# Sparkfun_Qwiic_Shield_for_ESP32.net
KiCad netlist of a schematic drawn in EAGLE
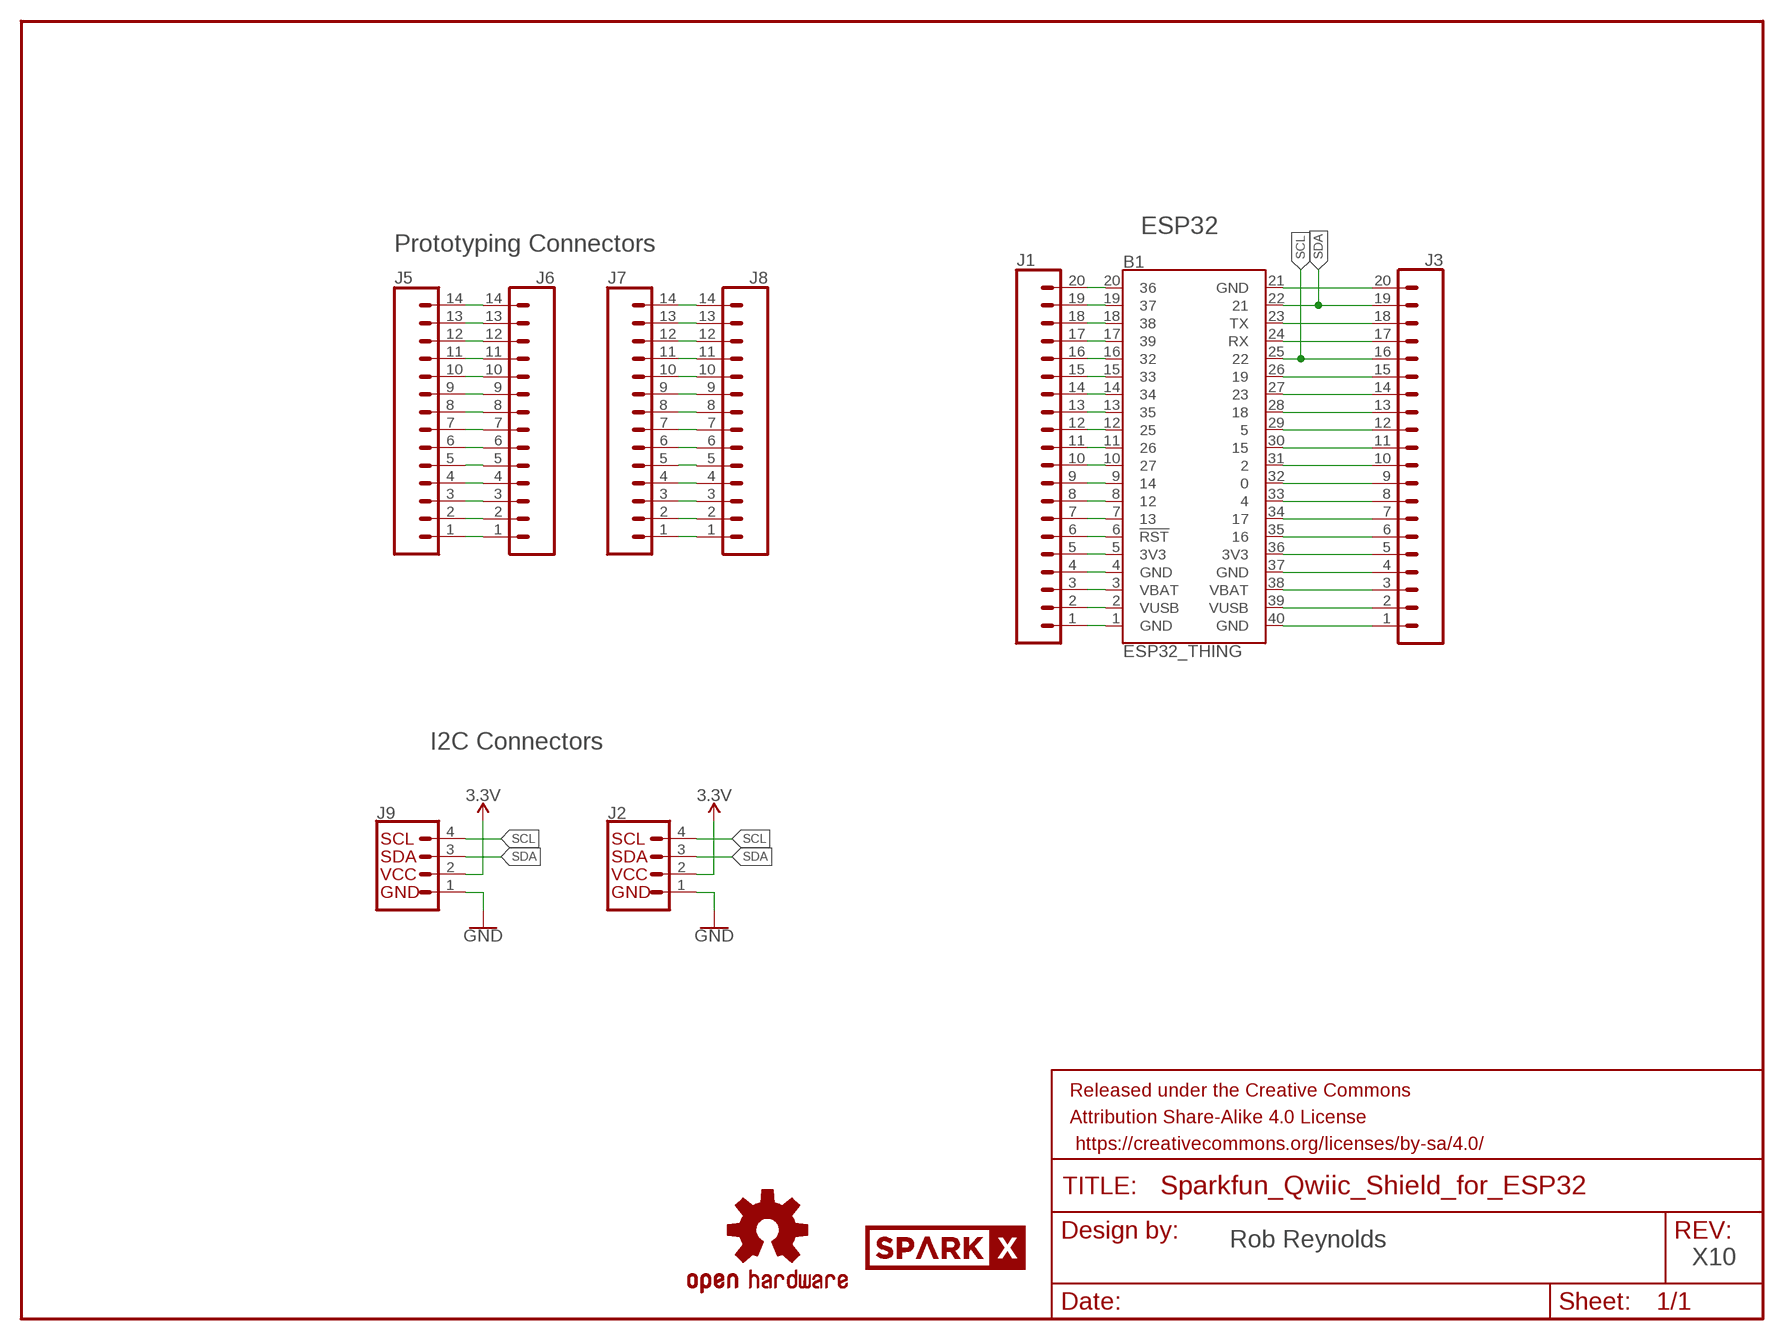
[diagram p0: schematic, sheet 1]

(export (version "E")
  (design (tool "Eeschema 10.0.6"))
  (components
    (comp (ref "B1")
      (value "ESP32_THING")
      (footprint "eagle-import:ESP32_THING")
      (libsource (lib "eagle-import") (part "ESP32_THING"))
    )
    (comp (ref "FRAME1")
      (value "FRAME-LETTERNO_PACKAGE")
      (footprint "eagle-import:DUMMY")
      (fields (field (name "DESIGNER") "Nobody"))
      (libsource (lib "eagle-import") (part "FRAME-LETTERNO_PACKAGE"))
    )
    (comp (ref "J1")
      (value "CONN_20NOSILK")
      (footprint "eagle-import:1X20_NOSILK")
      (libsource (lib "eagle-import") (part "CONN_20NOSILK"))
    )
    (comp (ref "J2")
      (value "I2C_STANDARDJS-1MM")
      (footprint "eagle-import:1X04_1MM_RA")
      (libsource (lib "eagle-import") (part "I2C_STANDARDJS-1MM"))
    )
    (comp (ref "J3")
      (value "CONN_20NOSILK")
      (footprint "eagle-import:1X20_NOSILK")
      (libsource (lib "eagle-import") (part "CONN_20NOSILK"))
    )
    (comp (ref "J5")
      (value "CONN_14NO_SILK")
      (footprint "eagle-import:1X14_NO_SILK")
      (libsource (lib "eagle-import") (part "CONN_14NO_SILK"))
    )
    (comp (ref "J6")
      (value "CONN_14NO_SILK")
      (footprint "eagle-import:1X14_NO_SILK")
      (libsource (lib "eagle-import") (part "CONN_14NO_SILK"))
    )
    (comp (ref "J7")
      (value "CONN_14NO_SILK")
      (footprint "eagle-import:1X14_NO_SILK")
      (libsource (lib "eagle-import") (part "CONN_14NO_SILK"))
    )
    (comp (ref "J8")
      (value "CONN_14NO_SILK")
      (footprint "eagle-import:1X14_NO_SILK")
      (libsource (lib "eagle-import") (part "CONN_14NO_SILK"))
    )
    (comp (ref "J9")
      (value "I2C_STANDARDJS-1MM")
      (footprint "eagle-import:1X04_1MM_RA")
      (libsource (lib "eagle-import") (part "I2C_STANDARDJS-1MM"))
    )
    (comp (ref "LOGO1")
      (value "OSHW-LOGOMINI")
      (footprint "eagle-import:OSHW-LOGO-MINI")
      (libsource (lib "eagle-import") (part "OSHW-LOGOMINI"))
    )
    (comp (ref "U$1")
      (value "SPARKX-LOGO3")
      (footprint "eagle-import:SPARKX-SMALL")
      (libsource (lib "eagle-import") (part "SPARKX-LOGO3"))
    )
  )
  (nets
    (net (code "1") (name "/VBAT") (class "Default")
      (node (ref "B1") (pin "3") (pinfunction "VBAT_3") (pintype "bidirectional"))
      (node (ref "B1") (pin "38") (pinfunction "VBAT_38") (pintype "bidirectional"))
      (node (ref "J1") (pin "3") (pinfunction "3_3") (pintype "passive"))
      (node (ref "J3") (pin "3") (pinfunction "3_3") (pintype "passive"))
    )
    (net (code "2") (name "/VUSB") (class "Default")
      (node (ref "B1") (pin "2") (pinfunction "VUSB_2") (pintype "bidirectional"))
      (node (ref "B1") (pin "39") (pinfunction "VUSB_39") (pintype "bidirectional"))
      (node (ref "J1") (pin "2") (pinfunction "2_2") (pintype "passive"))
      (node (ref "J3") (pin "2") (pinfunction "2_2") (pintype "passive"))
    )
    (net (code "3") (name "3.3V") (class "Default")
      (node (ref "B1") (pin "36") (pinfunction "3V3_36") (pintype "bidirectional"))
      (node (ref "B1") (pin "5") (pinfunction "3V3_5") (pintype "bidirectional"))
      (node (ref "J1") (pin "5") (pinfunction "5_5") (pintype "passive"))
      (node (ref "J2") (pin "2") (pinfunction "VCC_2") (pintype "power_in"))
      (node (ref "J3") (pin "5") (pinfunction "5_5") (pintype "passive"))
      (node (ref "J9") (pin "2") (pinfunction "VCC_2") (pintype "power_in"))
    )
    (net (code "4") (name "GND") (class "Default")
      (node (ref "B1") (pin "1") (pinfunction "GND_1") (pintype "bidirectional"))
      (node (ref "B1") (pin "21") (pinfunction "GND_21") (pintype "bidirectional"))
      (node (ref "B1") (pin "37") (pinfunction "GND_37") (pintype "bidirectional"))
      (node (ref "B1") (pin "4") (pinfunction "GND_4") (pintype "bidirectional"))
      (node (ref "B1") (pin "40") (pinfunction "GND_40") (pintype "bidirectional"))
      (node (ref "J1") (pin "1") (pinfunction "1_1") (pintype "passive"))
      (node (ref "J1") (pin "4") (pinfunction "4_4") (pintype "passive"))
      (node (ref "J2") (pin "1") (pinfunction "GND_1") (pintype "power_in"))
      (node (ref "J3") (pin "1") (pinfunction "1_1") (pintype "passive"))
      (node (ref "J3") (pin "20") (pinfunction "20_20") (pintype "passive"))
      (node (ref "J3") (pin "4") (pinfunction "4_4") (pintype "passive"))
      (node (ref "J9") (pin "1") (pinfunction "GND_1") (pintype "power_in"))
    )
    (net (code "5") (name "Net-(B1-0)") (class "Default")
      (node (ref "B1") (pin "32") (pinfunction "0_32") (pintype "bidirectional"))
      (node (ref "J3") (pin "9") (pinfunction "9_9") (pintype "passive"))
    )
    (net (code "6") (name "Net-(B1-2)") (class "Default")
      (node (ref "B1") (pin "31") (pinfunction "2_31") (pintype "bidirectional"))
      (node (ref "J3") (pin "10") (pinfunction "10_10") (pintype "passive"))
    )
    (net (code "7") (name "Net-(B1-4)") (class "Default")
      (node (ref "B1") (pin "33") (pinfunction "4_33") (pintype "bidirectional"))
      (node (ref "J3") (pin "8") (pinfunction "8_8") (pintype "passive"))
    )
    (net (code "8") (name "Net-(B1-5)") (class "Default")
      (node (ref "B1") (pin "29") (pinfunction "5_29") (pintype "bidirectional"))
      (node (ref "J3") (pin "12") (pinfunction "12_12") (pintype "passive"))
    )
    (net (code "9") (name "Net-(B1-12)") (class "Default")
      (node (ref "B1") (pin "8") (pinfunction "12_8") (pintype "bidirectional"))
      (node (ref "J1") (pin "8") (pinfunction "8_8") (pintype "passive"))
    )
    (net (code "10") (name "Net-(B1-13)") (class "Default")
      (node (ref "B1") (pin "7") (pinfunction "13_7") (pintype "bidirectional"))
      (node (ref "J1") (pin "7") (pinfunction "7_7") (pintype "passive"))
    )
    (net (code "11") (name "Net-(B1-14)") (class "Default")
      (node (ref "B1") (pin "9") (pinfunction "14_9") (pintype "bidirectional"))
      (node (ref "J1") (pin "9") (pinfunction "9_9") (pintype "passive"))
    )
    (net (code "12") (name "Net-(B1-15)") (class "Default")
      (node (ref "B1") (pin "30") (pinfunction "15_30") (pintype "bidirectional"))
      (node (ref "J3") (pin "11") (pinfunction "11_11") (pintype "passive"))
    )
    (net (code "13") (name "Net-(B1-16)") (class "Default")
      (node (ref "B1") (pin "35") (pinfunction "16_35") (pintype "bidirectional"))
      (node (ref "J3") (pin "6") (pinfunction "6_6") (pintype "passive"))
    )
    (net (code "14") (name "Net-(B1-17)") (class "Default")
      (node (ref "B1") (pin "34") (pinfunction "17_34") (pintype "bidirectional"))
      (node (ref "J3") (pin "7") (pinfunction "7_7") (pintype "passive"))
    )
    (net (code "15") (name "Net-(B1-18)") (class "Default")
      (node (ref "B1") (pin "28") (pinfunction "18_28") (pintype "bidirectional"))
      (node (ref "J3") (pin "13") (pinfunction "13_13") (pintype "passive"))
    )
    (net (code "16") (name "Net-(B1-19)") (class "Default")
      (node (ref "B1") (pin "26") (pinfunction "19_26") (pintype "bidirectional"))
      (node (ref "J3") (pin "15") (pinfunction "15_15") (pintype "passive"))
    )
    (net (code "17") (name "Net-(B1-23)") (class "Default")
      (node (ref "B1") (pin "27") (pinfunction "23_27") (pintype "bidirectional"))
      (node (ref "J3") (pin "14") (pinfunction "14_14") (pintype "passive"))
    )
    (net (code "18") (name "Net-(B1-25)") (class "Default")
      (node (ref "B1") (pin "12") (pinfunction "25_12") (pintype "bidirectional"))
      (node (ref "J1") (pin "12") (pinfunction "12_12") (pintype "passive"))
    )
    (net (code "19") (name "Net-(B1-26)") (class "Default")
      (node (ref "B1") (pin "11") (pinfunction "26_11") (pintype "bidirectional"))
      (node (ref "J1") (pin "11") (pinfunction "11_11") (pintype "passive"))
    )
    (net (code "20") (name "Net-(B1-27)") (class "Default")
      (node (ref "B1") (pin "10") (pinfunction "27_10") (pintype "bidirectional"))
      (node (ref "J1") (pin "10") (pinfunction "10_10") (pintype "passive"))
    )
    (net (code "21") (name "Net-(B1-32)") (class "Default")
      (node (ref "B1") (pin "16") (pinfunction "32_16") (pintype "bidirectional"))
      (node (ref "J1") (pin "16") (pinfunction "16_16") (pintype "passive"))
    )
    (net (code "22") (name "Net-(B1-33)") (class "Default")
      (node (ref "B1") (pin "15") (pinfunction "33_15") (pintype "bidirectional"))
      (node (ref "J1") (pin "15") (pinfunction "15_15") (pintype "passive"))
    )
    (net (code "23") (name "Net-(B1-34)") (class "Default")
      (node (ref "B1") (pin "14") (pinfunction "34_14") (pintype "bidirectional"))
      (node (ref "J1") (pin "14") (pinfunction "14_14") (pintype "passive"))
    )
    (net (code "24") (name "Net-(B1-35)") (class "Default")
      (node (ref "B1") (pin "13") (pinfunction "35_13") (pintype "bidirectional"))
      (node (ref "J1") (pin "13") (pinfunction "13_13") (pintype "passive"))
    )
    (net (code "25") (name "Net-(B1-36)") (class "Default")
      (node (ref "B1") (pin "20") (pinfunction "36_20") (pintype "bidirectional"))
      (node (ref "J1") (pin "20") (pinfunction "20_20") (pintype "passive"))
    )
    (net (code "26") (name "Net-(B1-37)") (class "Default")
      (node (ref "B1") (pin "19") (pinfunction "37_19") (pintype "bidirectional"))
      (node (ref "J1") (pin "19") (pinfunction "19_19") (pintype "passive"))
    )
    (net (code "27") (name "Net-(B1-38)") (class "Default")
      (node (ref "B1") (pin "18") (pinfunction "38_18") (pintype "bidirectional"))
      (node (ref "J1") (pin "18") (pinfunction "18_18") (pintype "passive"))
    )
    (net (code "28") (name "Net-(B1-39)") (class "Default")
      (node (ref "B1") (pin "17") (pinfunction "39_17") (pintype "bidirectional"))
      (node (ref "J1") (pin "17") (pinfunction "17_17") (pintype "passive"))
    )
    (net (code "29") (name "Net-(B1-RX)") (class "Default")
      (node (ref "B1") (pin "24") (pinfunction "RX_24") (pintype "bidirectional"))
      (node (ref "J3") (pin "17") (pinfunction "17_17") (pintype "passive"))
    )
    (net (code "30") (name "Net-(B1-TX)") (class "Default")
      (node (ref "B1") (pin "23") (pinfunction "TX_23") (pintype "bidirectional"))
      (node (ref "J3") (pin "18") (pinfunction "18_18") (pintype "passive"))
    )
    (net (code "31") (name "Net-(B1-~{RST})") (class "Default")
      (node (ref "B1") (pin "6") (pinfunction "~{RST}_6") (pintype "bidirectional"))
      (node (ref "J1") (pin "6") (pinfunction "6_6") (pintype "passive"))
    )
    (net (code "32") (name "Net-(J5-Pad1)") (class "Default")
      (node (ref "J5") (pin "1") (pinfunction "1_1") (pintype "passive"))
      (node (ref "J6") (pin "1") (pinfunction "1_1") (pintype "passive"))
    )
    (net (code "33") (name "Net-(J5-Pad2)") (class "Default")
      (node (ref "J5") (pin "2") (pinfunction "2_2") (pintype "passive"))
      (node (ref "J6") (pin "2") (pinfunction "2_2") (pintype "passive"))
    )
    (net (code "34") (name "Net-(J5-Pad3)") (class "Default")
      (node (ref "J5") (pin "3") (pinfunction "3_3") (pintype "passive"))
      (node (ref "J6") (pin "3") (pinfunction "3_3") (pintype "passive"))
    )
    (net (code "35") (name "Net-(J5-Pad4)") (class "Default")
      (node (ref "J5") (pin "4") (pinfunction "4_4") (pintype "passive"))
      (node (ref "J6") (pin "4") (pinfunction "4_4") (pintype "passive"))
    )
    (net (code "36") (name "Net-(J5-Pad5)") (class "Default")
      (node (ref "J5") (pin "5") (pinfunction "5_5") (pintype "passive"))
      (node (ref "J6") (pin "5") (pinfunction "5_5") (pintype "passive"))
    )
    (net (code "37") (name "Net-(J5-Pad6)") (class "Default")
      (node (ref "J5") (pin "6") (pinfunction "6_6") (pintype "passive"))
      (node (ref "J6") (pin "6") (pinfunction "6_6") (pintype "passive"))
    )
    (net (code "38") (name "Net-(J5-Pad7)") (class "Default")
      (node (ref "J5") (pin "7") (pinfunction "7_7") (pintype "passive"))
      (node (ref "J6") (pin "7") (pinfunction "7_7") (pintype "passive"))
    )
    (net (code "39") (name "Net-(J5-Pad8)") (class "Default")
      (node (ref "J5") (pin "8") (pinfunction "8_8") (pintype "passive"))
      (node (ref "J6") (pin "8") (pinfunction "8_8") (pintype "passive"))
    )
    (net (code "40") (name "Net-(J5-Pad9)") (class "Default")
      (node (ref "J5") (pin "9") (pinfunction "9_9") (pintype "passive"))
      (node (ref "J6") (pin "9") (pinfunction "9_9") (pintype "passive"))
    )
    (net (code "41") (name "Net-(J5-Pad10)") (class "Default")
      (node (ref "J5") (pin "10") (pinfunction "10_10") (pintype "passive"))
      (node (ref "J6") (pin "10") (pinfunction "10_10") (pintype "passive"))
    )
    (net (code "42") (name "Net-(J5-Pad11)") (class "Default")
      (node (ref "J5") (pin "11") (pinfunction "11_11") (pintype "passive"))
      (node (ref "J6") (pin "11") (pinfunction "11_11") (pintype "passive"))
    )
    (net (code "43") (name "Net-(J5-Pad12)") (class "Default")
      (node (ref "J5") (pin "12") (pinfunction "12_12") (pintype "passive"))
      (node (ref "J6") (pin "12") (pinfunction "12_12") (pintype "passive"))
    )
    (net (code "44") (name "Net-(J5-Pad13)") (class "Default")
      (node (ref "J5") (pin "13") (pinfunction "13_13") (pintype "passive"))
      (node (ref "J6") (pin "13") (pinfunction "13_13") (pintype "passive"))
    )
    (net (code "45") (name "Net-(J5-Pad14)") (class "Default")
      (node (ref "J5") (pin "14") (pinfunction "14_14") (pintype "passive"))
      (node (ref "J6") (pin "14") (pinfunction "14_14") (pintype "passive"))
    )
    (net (code "46") (name "Net-(J7-Pad1)") (class "Default")
      (node (ref "J7") (pin "1") (pinfunction "1_1") (pintype "passive"))
      (node (ref "J8") (pin "1") (pinfunction "1_1") (pintype "passive"))
    )
    (net (code "47") (name "Net-(J7-Pad2)") (class "Default")
      (node (ref "J7") (pin "2") (pinfunction "2_2") (pintype "passive"))
      (node (ref "J8") (pin "2") (pinfunction "2_2") (pintype "passive"))
    )
    (net (code "48") (name "Net-(J7-Pad3)") (class "Default")
      (node (ref "J7") (pin "3") (pinfunction "3_3") (pintype "passive"))
      (node (ref "J8") (pin "3") (pinfunction "3_3") (pintype "passive"))
    )
    (net (code "49") (name "Net-(J7-Pad4)") (class "Default")
      (node (ref "J7") (pin "4") (pinfunction "4_4") (pintype "passive"))
      (node (ref "J8") (pin "4") (pinfunction "4_4") (pintype "passive"))
    )
    (net (code "50") (name "Net-(J7-Pad5)") (class "Default")
      (node (ref "J7") (pin "5") (pinfunction "5_5") (pintype "passive"))
      (node (ref "J8") (pin "5") (pinfunction "5_5") (pintype "passive"))
    )
    (net (code "51") (name "Net-(J7-Pad6)") (class "Default")
      (node (ref "J7") (pin "6") (pinfunction "6_6") (pintype "passive"))
      (node (ref "J8") (pin "6") (pinfunction "6_6") (pintype "passive"))
    )
    (net (code "52") (name "Net-(J7-Pad7)") (class "Default")
      (node (ref "J7") (pin "7") (pinfunction "7_7") (pintype "passive"))
      (node (ref "J8") (pin "7") (pinfunction "7_7") (pintype "passive"))
    )
    (net (code "53") (name "Net-(J7-Pad8)") (class "Default")
      (node (ref "J7") (pin "8") (pinfunction "8_8") (pintype "passive"))
      (node (ref "J8") (pin "8") (pinfunction "8_8") (pintype "passive"))
    )
    (net (code "54") (name "Net-(J7-Pad9)") (class "Default")
      (node (ref "J7") (pin "9") (pinfunction "9_9") (pintype "passive"))
      (node (ref "J8") (pin "9") (pinfunction "9_9") (pintype "passive"))
    )
    (net (code "55") (name "Net-(J7-Pad10)") (class "Default")
      (node (ref "J7") (pin "10") (pinfunction "10_10") (pintype "passive"))
      (node (ref "J8") (pin "10") (pinfunction "10_10") (pintype "passive"))
    )
    (net (code "56") (name "Net-(J7-Pad11)") (class "Default")
      (node (ref "J7") (pin "11") (pinfunction "11_11") (pintype "passive"))
      (node (ref "J8") (pin "11") (pinfunction "11_11") (pintype "passive"))
    )
    (net (code "57") (name "Net-(J7-Pad12)") (class "Default")
      (node (ref "J7") (pin "12") (pinfunction "12_12") (pintype "passive"))
      (node (ref "J8") (pin "12") (pinfunction "12_12") (pintype "passive"))
    )
    (net (code "58") (name "Net-(J7-Pad13)") (class "Default")
      (node (ref "J7") (pin "13") (pinfunction "13_13") (pintype "passive"))
      (node (ref "J8") (pin "13") (pinfunction "13_13") (pintype "passive"))
    )
    (net (code "59") (name "Net-(J7-Pad14)") (class "Default")
      (node (ref "J7") (pin "14") (pinfunction "14_14") (pintype "passive"))
      (node (ref "J8") (pin "14") (pinfunction "14_14") (pintype "passive"))
    )
    (net (code "60") (name "SCL") (class "Default")
      (node (ref "B1") (pin "25") (pinfunction "22_25") (pintype "bidirectional"))
      (node (ref "J2") (pin "4") (pinfunction "SCL_4") (pintype "passive"))
      (node (ref "J3") (pin "16") (pinfunction "16_16") (pintype "passive"))
      (node (ref "J9") (pin "4") (pinfunction "SCL_4") (pintype "passive"))
    )
    (net (code "61") (name "SDA") (class "Default")
      (node (ref "B1") (pin "22") (pinfunction "21_22") (pintype "bidirectional"))
      (node (ref "J2") (pin "3") (pinfunction "SDA_3") (pintype "passive"))
      (node (ref "J3") (pin "19") (pinfunction "19_19") (pintype "passive"))
      (node (ref "J9") (pin "3") (pinfunction "SDA_3") (pintype "passive"))
    )
  )
)
